# R131C.net
KiCad netlist of a schematic drawn in EAGLE
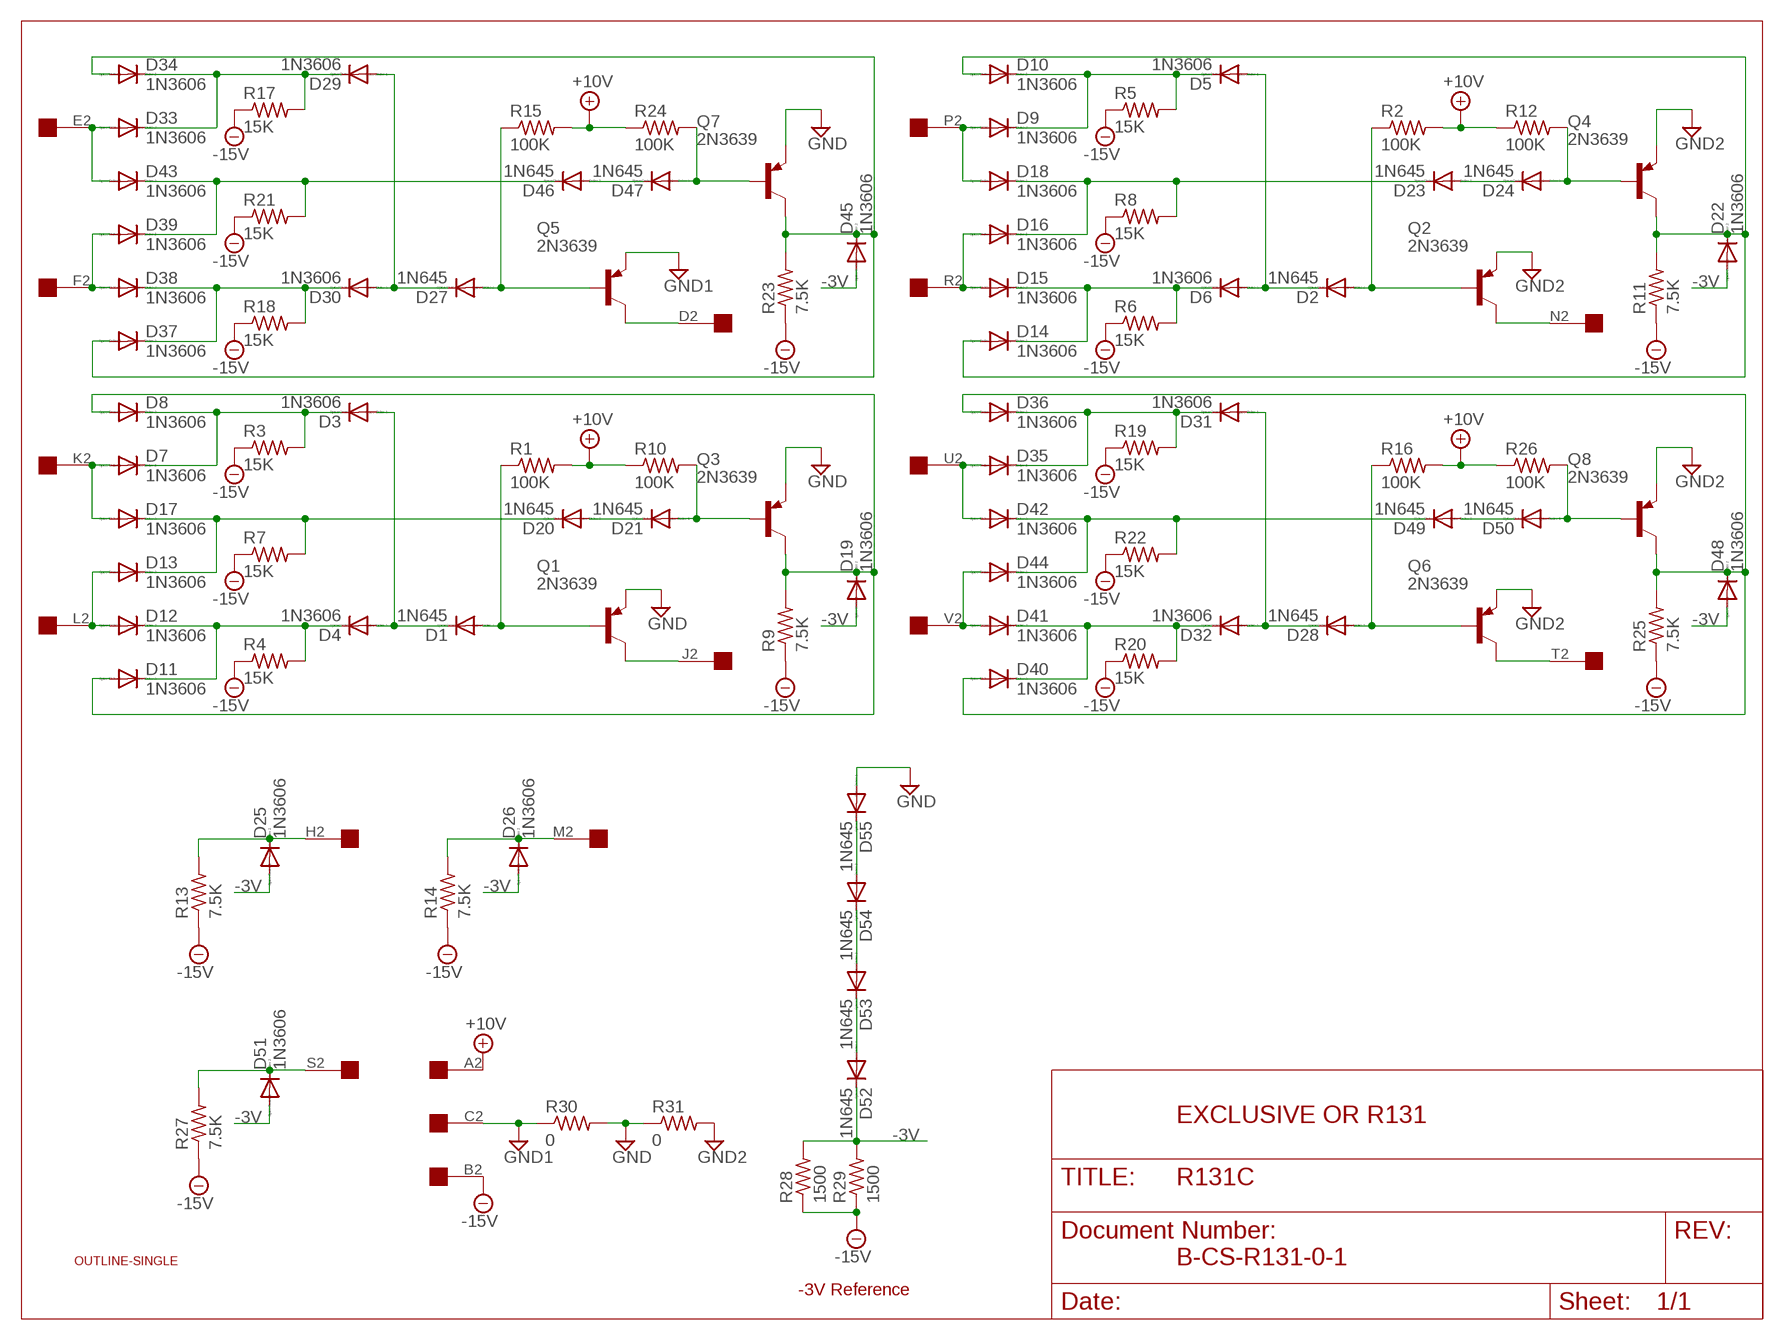
[diagram p0: schematic, sheet 1]

(export (version "E")
  (design (tool "Eeschema 10.0.6"))
  (components
    (comp (ref "D1")
      (value "1N645")
      (footprint "eagle-import:DO35-10")
      (libsource (lib "eagle-import") (part "1N4148DO35-10"))
    )
    (comp (ref "D2")
      (value "1N645")
      (footprint "eagle-import:DO35-10")
      (libsource (lib "eagle-import") (part "1N4148DO35-10"))
    )
    (comp (ref "D3")
      (value "1N3606")
      (footprint "eagle-import:DO35-10")
      (libsource (lib "eagle-import") (part "1N4148DO35-10"))
    )
    (comp (ref "D4")
      (value "1N3606")
      (footprint "eagle-import:DO35-10")
      (libsource (lib "eagle-import") (part "1N4148DO35-10"))
    )
    (comp (ref "D5")
      (value "1N3606")
      (footprint "eagle-import:DO35-10")
      (libsource (lib "eagle-import") (part "1N4148DO35-10"))
    )
    (comp (ref "D6")
      (value "1N3606")
      (footprint "eagle-import:DO35-10")
      (libsource (lib "eagle-import") (part "1N4148DO35-10"))
    )
    (comp (ref "D7")
      (value "1N3606")
      (footprint "eagle-import:DO35-10")
      (libsource (lib "eagle-import") (part "1N4148DO35-10"))
    )
    (comp (ref "D8")
      (value "1N3606")
      (footprint "eagle-import:DO35-10")
      (libsource (lib "eagle-import") (part "1N4148DO35-10"))
    )
    (comp (ref "D9")
      (value "1N3606")
      (footprint "eagle-import:DO35-10")
      (libsource (lib "eagle-import") (part "1N4148DO35-10"))
    )
    (comp (ref "D10")
      (value "1N3606")
      (footprint "eagle-import:DO35-10")
      (libsource (lib "eagle-import") (part "1N4148DO35-10"))
    )
    (comp (ref "D11")
      (value "1N3606")
      (footprint "eagle-import:DO35-10")
      (libsource (lib "eagle-import") (part "1N4148DO35-10"))
    )
    (comp (ref "D12")
      (value "1N3606")
      (footprint "eagle-import:DO35-10")
      (libsource (lib "eagle-import") (part "1N4148DO35-10"))
    )
    (comp (ref "D13")
      (value "1N3606")
      (footprint "eagle-import:DO35-10")
      (libsource (lib "eagle-import") (part "1N4148DO35-10"))
    )
    (comp (ref "D14")
      (value "1N3606")
      (footprint "eagle-import:DO35-10")
      (libsource (lib "eagle-import") (part "1N4148DO35-10"))
    )
    (comp (ref "D15")
      (value "1N3606")
      (footprint "eagle-import:DO35-10")
      (libsource (lib "eagle-import") (part "1N4148DO35-10"))
    )
    (comp (ref "D16")
      (value "1N3606")
      (footprint "eagle-import:DO35-10")
      (libsource (lib "eagle-import") (part "1N4148DO35-10"))
    )
    (comp (ref "D17")
      (value "1N3606")
      (footprint "eagle-import:DO35-10")
      (libsource (lib "eagle-import") (part "1N4148DO35-10"))
    )
    (comp (ref "D18")
      (value "1N3606")
      (footprint "eagle-import:DO35-10")
      (libsource (lib "eagle-import") (part "1N4148DO35-10"))
    )
    (comp (ref "D19")
      (value "1N3606")
      (footprint "eagle-import:DO35-10")
      (libsource (lib "eagle-import") (part "1N4148DO35-10"))
    )
    (comp (ref "D20")
      (value "1N645")
      (footprint "eagle-import:DO35-10")
      (libsource (lib "eagle-import") (part "1N4148DO35-10"))
    )
    (comp (ref "D21")
      (value "1N645")
      (footprint "eagle-import:DO35-10")
      (libsource (lib "eagle-import") (part "1N4148DO35-10"))
    )
    (comp (ref "D22")
      (value "1N3606")
      (footprint "eagle-import:DO35-10")
      (libsource (lib "eagle-import") (part "1N4148DO35-10"))
    )
    (comp (ref "D23")
      (value "1N645")
      (footprint "eagle-import:DO35-10")
      (libsource (lib "eagle-import") (part "1N4148DO35-10"))
    )
    (comp (ref "D24")
      (value "1N645")
      (footprint "eagle-import:DO35-10")
      (libsource (lib "eagle-import") (part "1N4148DO35-10"))
    )
    (comp (ref "D25")
      (value "1N3606")
      (footprint "eagle-import:DO35-10")
      (libsource (lib "eagle-import") (part "1N4148DO35-10"))
    )
    (comp (ref "D26")
      (value "1N3606")
      (footprint "eagle-import:DO35-10")
      (libsource (lib "eagle-import") (part "1N4148DO35-10"))
    )
    (comp (ref "D27")
      (value "1N645")
      (footprint "eagle-import:DO35-10")
      (libsource (lib "eagle-import") (part "1N4148DO35-10"))
    )
    (comp (ref "D28")
      (value "1N645")
      (footprint "eagle-import:DO35-10")
      (libsource (lib "eagle-import") (part "1N4148DO35-10"))
    )
    (comp (ref "D29")
      (value "1N3606")
      (footprint "eagle-import:DO35-10")
      (libsource (lib "eagle-import") (part "1N4148DO35-10"))
    )
    (comp (ref "D30")
      (value "1N3606")
      (footprint "eagle-import:DO35-10")
      (libsource (lib "eagle-import") (part "1N4148DO35-10"))
    )
    (comp (ref "D31")
      (value "1N3606")
      (footprint "eagle-import:DO35-10")
      (libsource (lib "eagle-import") (part "1N4148DO35-10"))
    )
    (comp (ref "D32")
      (value "1N3606")
      (footprint "eagle-import:DO35-10")
      (libsource (lib "eagle-import") (part "1N4148DO35-10"))
    )
    (comp (ref "D33")
      (value "1N3606")
      (footprint "eagle-import:DO35-10")
      (libsource (lib "eagle-import") (part "1N4148DO35-10"))
    )
    (comp (ref "D34")
      (value "1N3606")
      (footprint "eagle-import:DO35-10")
      (libsource (lib "eagle-import") (part "1N4148DO35-10"))
    )
    (comp (ref "D35")
      (value "1N3606")
      (footprint "eagle-import:DO35-10")
      (libsource (lib "eagle-import") (part "1N4148DO35-10"))
    )
    (comp (ref "D36")
      (value "1N3606")
      (footprint "eagle-import:DO35-10")
      (libsource (lib "eagle-import") (part "1N4148DO35-10"))
    )
    (comp (ref "D37")
      (value "1N3606")
      (footprint "eagle-import:DO35-10")
      (libsource (lib "eagle-import") (part "1N4148DO35-10"))
    )
    (comp (ref "D38")
      (value "1N3606")
      (footprint "eagle-import:DO35-10")
      (libsource (lib "eagle-import") (part "1N4148DO35-10"))
    )
    (comp (ref "D39")
      (value "1N3606")
      (footprint "eagle-import:DO35-10")
      (libsource (lib "eagle-import") (part "1N4148DO35-10"))
    )
    (comp (ref "D40")
      (value "1N3606")
      (footprint "eagle-import:DO35-10")
      (libsource (lib "eagle-import") (part "1N4148DO35-10"))
    )
    (comp (ref "D41")
      (value "1N3606")
      (footprint "eagle-import:DO35-10")
      (libsource (lib "eagle-import") (part "1N4148DO35-10"))
    )
    (comp (ref "D42")
      (value "1N3606")
      (footprint "eagle-import:DO35-10")
      (libsource (lib "eagle-import") (part "1N4148DO35-10"))
    )
    (comp (ref "D43")
      (value "1N3606")
      (footprint "eagle-import:DO35-10")
      (libsource (lib "eagle-import") (part "1N4148DO35-10"))
    )
    (comp (ref "D44")
      (value "1N3606")
      (footprint "eagle-import:DO35-10")
      (libsource (lib "eagle-import") (part "1N4148DO35-10"))
    )
    (comp (ref "D45")
      (value "1N3606")
      (footprint "eagle-import:DO35-10")
      (libsource (lib "eagle-import") (part "1N4148DO35-10"))
    )
    (comp (ref "D46")
      (value "1N645")
      (footprint "eagle-import:DO35-10")
      (libsource (lib "eagle-import") (part "1N4148DO35-10"))
    )
    (comp (ref "D47")
      (value "1N645")
      (footprint "eagle-import:DO35-10")
      (libsource (lib "eagle-import") (part "1N4148DO35-10"))
    )
    (comp (ref "D48")
      (value "1N3606")
      (footprint "eagle-import:DO35-10")
      (libsource (lib "eagle-import") (part "1N4148DO35-10"))
    )
    (comp (ref "D49")
      (value "1N645")
      (footprint "eagle-import:DO35-10")
      (libsource (lib "eagle-import") (part "1N4148DO35-10"))
    )
    (comp (ref "D50")
      (value "1N645")
      (footprint "eagle-import:DO35-10")
      (libsource (lib "eagle-import") (part "1N4148DO35-10"))
    )
    (comp (ref "D51")
      (value "1N3606")
      (footprint "eagle-import:DO35-10")
      (libsource (lib "eagle-import") (part "1N4148DO35-10"))
    )
    (comp (ref "D52")
      (value "1N645")
      (footprint "eagle-import:DO35-10")
      (libsource (lib "eagle-import") (part "1N4148DO35-10"))
    )
    (comp (ref "D53")
      (value "1N645")
      (footprint "eagle-import:DO35-10")
      (libsource (lib "eagle-import") (part "1N4148DO35-10"))
    )
    (comp (ref "D54")
      (value "1N645")
      (footprint "eagle-import:DO35-10")
      (libsource (lib "eagle-import") (part "1N4148DO35-10"))
    )
    (comp (ref "D55")
      (value "1N645")
      (footprint "eagle-import:DO35-10")
      (libsource (lib "eagle-import") (part "1N4148DO35-10"))
    )
    (comp (ref "Q1")
      (value "2N3639")
      (footprint "eagle-import:TO39")
      (libsource (lib "eagle-import") (part "2N3637"))
    )
    (comp (ref "Q2")
      (value "2N3639")
      (footprint "eagle-import:TO39")
      (libsource (lib "eagle-import") (part "2N3637"))
    )
    (comp (ref "Q3")
      (value "2N3639")
      (footprint "eagle-import:TO39")
      (libsource (lib "eagle-import") (part "2N3637"))
    )
    (comp (ref "Q4")
      (value "2N3639")
      (footprint "eagle-import:TO39")
      (libsource (lib "eagle-import") (part "2N3637"))
    )
    (comp (ref "Q5")
      (value "2N3639")
      (footprint "eagle-import:TO39")
      (libsource (lib "eagle-import") (part "2N3637"))
    )
    (comp (ref "Q6")
      (value "2N3639")
      (footprint "eagle-import:TO39")
      (libsource (lib "eagle-import") (part "2N3637"))
    )
    (comp (ref "Q7")
      (value "2N3639")
      (footprint "eagle-import:TO39")
      (libsource (lib "eagle-import") (part "2N3637"))
    )
    (comp (ref "Q8")
      (value "2N3639")
      (footprint "eagle-import:TO39")
      (libsource (lib "eagle-import") (part "2N3637"))
    )
    (comp (ref "R1")
      (value "100K")
      (footprint "eagle-import:0207_10")
      (libsource (lib "eagle-import") (part "R-US_0207/10"))
    )
    (comp (ref "R2")
      (value "100K")
      (footprint "eagle-import:0207_10")
      (libsource (lib "eagle-import") (part "R-US_0207/10"))
    )
    (comp (ref "R3")
      (value "15K")
      (footprint "eagle-import:0207_10")
      (libsource (lib "eagle-import") (part "R-US_0207/10"))
    )
    (comp (ref "R4")
      (value "15K")
      (footprint "eagle-import:0207_10")
      (libsource (lib "eagle-import") (part "R-US_0207/10"))
    )
    (comp (ref "R5")
      (value "15K")
      (footprint "eagle-import:0207_10")
      (libsource (lib "eagle-import") (part "R-US_0207/10"))
    )
    (comp (ref "R6")
      (value "15K")
      (footprint "eagle-import:0207_10")
      (libsource (lib "eagle-import") (part "R-US_0207/10"))
    )
    (comp (ref "R7")
      (value "15K")
      (footprint "eagle-import:0207_10")
      (libsource (lib "eagle-import") (part "R-US_0207/10"))
    )
    (comp (ref "R8")
      (value "15K")
      (footprint "eagle-import:0207_10")
      (libsource (lib "eagle-import") (part "R-US_0207/10"))
    )
    (comp (ref "R9")
      (value "7.5K")
      (footprint "eagle-import:0207_10")
      (libsource (lib "eagle-import") (part "R-US_0207/10"))
    )
    (comp (ref "R10")
      (value "100K")
      (footprint "eagle-import:0207_10")
      (libsource (lib "eagle-import") (part "R-US_0207/10"))
    )
    (comp (ref "R11")
      (value "7.5K")
      (footprint "eagle-import:0207_10")
      (libsource (lib "eagle-import") (part "R-US_0207/10"))
    )
    (comp (ref "R12")
      (value "100K")
      (footprint "eagle-import:0207_10")
      (libsource (lib "eagle-import") (part "R-US_0207/10"))
    )
    (comp (ref "R13")
      (value "7.5K")
      (footprint "eagle-import:0207_10")
      (libsource (lib "eagle-import") (part "R-US_0207/10"))
    )
    (comp (ref "R14")
      (value "7.5K")
      (footprint "eagle-import:0207_10")
      (libsource (lib "eagle-import") (part "R-US_0207/10"))
    )
    (comp (ref "R15")
      (value "100K")
      (footprint "eagle-import:0207_10")
      (libsource (lib "eagle-import") (part "R-US_0207/10"))
    )
    (comp (ref "R16")
      (value "100K")
      (footprint "eagle-import:0207_10")
      (libsource (lib "eagle-import") (part "R-US_0207/10"))
    )
    (comp (ref "R17")
      (value "15K")
      (footprint "eagle-import:0207_10")
      (libsource (lib "eagle-import") (part "R-US_0207/10"))
    )
    (comp (ref "R18")
      (value "15K")
      (footprint "eagle-import:0207_10")
      (libsource (lib "eagle-import") (part "R-US_0207/10"))
    )
    (comp (ref "R19")
      (value "15K")
      (footprint "eagle-import:0207_10")
      (libsource (lib "eagle-import") (part "R-US_0207/10"))
    )
    (comp (ref "R20")
      (value "15K")
      (footprint "eagle-import:0207_10")
      (libsource (lib "eagle-import") (part "R-US_0207/10"))
    )
    (comp (ref "R21")
      (value "15K")
      (footprint "eagle-import:0207_10")
      (libsource (lib "eagle-import") (part "R-US_0207/10"))
    )
    (comp (ref "R22")
      (value "15K")
      (footprint "eagle-import:0207_10")
      (libsource (lib "eagle-import") (part "R-US_0207/10"))
    )
    (comp (ref "R23")
      (value "7.5K")
      (footprint "eagle-import:0207_10")
      (libsource (lib "eagle-import") (part "R-US_0207/10"))
    )
    (comp (ref "R24")
      (value "100K")
      (footprint "eagle-import:0207_10")
      (libsource (lib "eagle-import") (part "R-US_0207/10"))
    )
    (comp (ref "R25")
      (value "7.5K")
      (footprint "eagle-import:0207_10")
      (libsource (lib "eagle-import") (part "R-US_0207/10"))
    )
    (comp (ref "R26")
      (value "100K")
      (footprint "eagle-import:0207_10")
      (libsource (lib "eagle-import") (part "R-US_0207/10"))
    )
    (comp (ref "R27")
      (value "7.5K")
      (footprint "eagle-import:0207_10")
      (libsource (lib "eagle-import") (part "R-US_0207/10"))
    )
    (comp (ref "R28")
      (value "1500")
      (footprint "eagle-import:0207_10")
      (libsource (lib "eagle-import") (part "R-US_0207/10"))
    )
    (comp (ref "R29")
      (value "1500")
      (footprint "eagle-import:0207_10")
      (libsource (lib "eagle-import") (part "R-US_0207/10"))
    )
    (comp (ref "R30")
      (value "0")
      (footprint "eagle-import:0207_10")
      (libsource (lib "eagle-import") (part "R-US_0207/10"))
    )
    (comp (ref "R31")
      (value "0")
      (footprint "eagle-import:0207_10")
      (libsource (lib "eagle-import") (part "R-US_0207/10"))
    )
    (comp (ref "U$1")
      (value "OUTLINE-SINGLE")
      (footprint "eagle-import:SINGLE")
      (libsource (lib "eagle-import") (part "OUTLINE-SINGLE"))
    )
    (comp (ref "U$2")
      (value "EDGE-1")
      (footprint "eagle-import:EDGE-CON1")
      (libsource (lib "eagle-import") (part "EDGE-1"))
    )
  )
  (nets
    (net (code "1") (name "+10V") (class "Default")
      (node (ref "R1") (pin "2") (pinfunction "2_2") (pintype "passive"))
      (node (ref "R10") (pin "1") (pinfunction "1_1") (pintype "passive"))
      (node (ref "R12") (pin "1") (pinfunction "1_1") (pintype "passive"))
      (node (ref "R15") (pin "2") (pinfunction "2_2") (pintype "passive"))
      (node (ref "R16") (pin "2") (pinfunction "2_2") (pintype "passive"))
      (node (ref "R2") (pin "2") (pinfunction "2_2") (pintype "passive"))
      (node (ref "R24") (pin "1") (pinfunction "1_1") (pintype "passive"))
      (node (ref "R26") (pin "1") (pinfunction "1_1") (pintype "passive"))
      (node (ref "U$2") (pin "A2") (pinfunction "1_A2") (pintype "bidirectional"))
    )
    (net (code "2") (name "-15V") (class "Default")
      (node (ref "R11") (pin "1") (pinfunction "1_1") (pintype "passive"))
      (node (ref "R13") (pin "1") (pinfunction "1_1") (pintype "passive"))
      (node (ref "R14") (pin "1") (pinfunction "1_1") (pintype "passive"))
      (node (ref "R17") (pin "1") (pinfunction "1_1") (pintype "passive"))
      (node (ref "R18") (pin "1") (pinfunction "1_1") (pintype "passive"))
      (node (ref "R19") (pin "1") (pinfunction "1_1") (pintype "passive"))
      (node (ref "R20") (pin "1") (pinfunction "1_1") (pintype "passive"))
      (node (ref "R21") (pin "1") (pinfunction "1_1") (pintype "passive"))
      (node (ref "R22") (pin "1") (pinfunction "1_1") (pintype "passive"))
      (node (ref "R23") (pin "1") (pinfunction "1_1") (pintype "passive"))
      (node (ref "R25") (pin "1") (pinfunction "1_1") (pintype "passive"))
      (node (ref "R27") (pin "1") (pinfunction "1_1") (pintype "passive"))
      (node (ref "R28") (pin "1") (pinfunction "1_1") (pintype "passive"))
      (node (ref "R29") (pin "1") (pinfunction "1_1") (pintype "passive"))
      (node (ref "R3") (pin "1") (pinfunction "1_1") (pintype "passive"))
      (node (ref "R4") (pin "1") (pinfunction "1_1") (pintype "passive"))
      (node (ref "R5") (pin "1") (pinfunction "1_1") (pintype "passive"))
      (node (ref "R6") (pin "1") (pinfunction "1_1") (pintype "passive"))
      (node (ref "R7") (pin "1") (pinfunction "1_1") (pintype "passive"))
      (node (ref "R8") (pin "1") (pinfunction "1_1") (pintype "passive"))
      (node (ref "R9") (pin "1") (pinfunction "1_1") (pintype "passive"))
      (node (ref "U$2") (pin "B2") (pinfunction "1_B2") (pintype "bidirectional"))
    )
    (net (code "3") (name "/-3V") (class "Default")
      (node (ref "D19") (pin "A") (pinfunction "A_A") (pintype "passive"))
      (node (ref "D22") (pin "A") (pinfunction "A_A") (pintype "passive"))
      (node (ref "D25") (pin "A") (pinfunction "A_A") (pintype "passive"))
      (node (ref "D26") (pin "A") (pinfunction "A_A") (pintype "passive"))
      (node (ref "D45") (pin "A") (pinfunction "A_A") (pintype "passive"))
      (node (ref "D48") (pin "A") (pinfunction "A_A") (pintype "passive"))
      (node (ref "D51") (pin "A") (pinfunction "A_A") (pintype "passive"))
      (node (ref "D52") (pin "C") (pinfunction "C_C") (pintype "passive"))
      (node (ref "R28") (pin "2") (pinfunction "2_2") (pintype "passive"))
      (node (ref "R29") (pin "2") (pinfunction "2_2") (pintype "passive"))
    )
    (net (code "4") (name "GND") (class "Default")
      (node (ref "D55") (pin "A") (pinfunction "A_A") (pintype "passive"))
      (node (ref "Q1") (pin "1") (pinfunction "E_1") (pintype "passive"))
      (node (ref "Q3") (pin "1") (pinfunction "E_1") (pintype "passive"))
      (node (ref "Q7") (pin "1") (pinfunction "E_1") (pintype "passive"))
      (node (ref "R30") (pin "2") (pinfunction "2_2") (pintype "passive"))
      (node (ref "R31") (pin "1") (pinfunction "1_1") (pintype "passive"))
    )
    (net (code "5") (name "GND1") (class "Default")
      (node (ref "Q5") (pin "1") (pinfunction "E_1") (pintype "passive"))
      (node (ref "R30") (pin "1") (pinfunction "1_1") (pintype "passive"))
      (node (ref "U$2") (pin "C2") (pinfunction "1_C2") (pintype "bidirectional"))
    )
    (net (code "6") (name "GND2") (class "Default")
      (node (ref "Q2") (pin "1") (pinfunction "E_1") (pintype "passive"))
      (node (ref "Q4") (pin "1") (pinfunction "E_1") (pintype "passive"))
      (node (ref "Q6") (pin "1") (pinfunction "E_1") (pintype "passive"))
      (node (ref "Q8") (pin "1") (pinfunction "E_1") (pintype "passive"))
      (node (ref "R31") (pin "2") (pinfunction "2_2") (pintype "passive"))
    )
    (net (code "7") (name "Net-(D1-PadC)") (class "Default")
      (node (ref "D1") (pin "C") (pinfunction "C_C") (pintype "passive"))
      (node (ref "D3") (pin "A") (pinfunction "A_A") (pintype "passive"))
      (node (ref "D4") (pin "A") (pinfunction "A_A") (pintype "passive"))
    )
    (net (code "8") (name "Net-(D2-PadC)") (class "Default")
      (node (ref "D2") (pin "C") (pinfunction "C_C") (pintype "passive"))
      (node (ref "D5") (pin "A") (pinfunction "A_A") (pintype "passive"))
      (node (ref "D6") (pin "A") (pinfunction "A_A") (pintype "passive"))
    )
    (net (code "9") (name "Net-(D3-PadC)") (class "Default")
      (node (ref "D3") (pin "C") (pinfunction "C_C") (pintype "passive"))
      (node (ref "D7") (pin "C") (pinfunction "C_C") (pintype "passive"))
      (node (ref "D8") (pin "C") (pinfunction "C_C") (pintype "passive"))
      (node (ref "R3") (pin "2") (pinfunction "2_2") (pintype "passive"))
    )
    (net (code "10") (name "Net-(D10-PadC)") (class "Default")
      (node (ref "D10") (pin "C") (pinfunction "C_C") (pintype "passive"))
      (node (ref "D5") (pin "C") (pinfunction "C_C") (pintype "passive"))
      (node (ref "D9") (pin "C") (pinfunction "C_C") (pintype "passive"))
      (node (ref "R5") (pin "2") (pinfunction "2_2") (pintype "passive"))
    )
    (net (code "11") (name "Net-(D11-PadC)") (class "Default")
      (node (ref "D11") (pin "C") (pinfunction "C_C") (pintype "passive"))
      (node (ref "D12") (pin "C") (pinfunction "C_C") (pintype "passive"))
      (node (ref "D4") (pin "C") (pinfunction "C_C") (pintype "passive"))
      (node (ref "R4") (pin "2") (pinfunction "2_2") (pintype "passive"))
    )
    (net (code "12") (name "Net-(D13-PadC)") (class "Default")
      (node (ref "D13") (pin "C") (pinfunction "C_C") (pintype "passive"))
      (node (ref "D17") (pin "C") (pinfunction "C_C") (pintype "passive"))
      (node (ref "D20") (pin "C") (pinfunction "C_C") (pintype "passive"))
      (node (ref "R7") (pin "2") (pinfunction "2_2") (pintype "passive"))
    )
    (net (code "13") (name "Net-(D14-PadC)") (class "Default")
      (node (ref "D14") (pin "C") (pinfunction "C_C") (pintype "passive"))
      (node (ref "D15") (pin "C") (pinfunction "C_C") (pintype "passive"))
      (node (ref "D6") (pin "C") (pinfunction "C_C") (pintype "passive"))
      (node (ref "R6") (pin "2") (pinfunction "2_2") (pintype "passive"))
    )
    (net (code "14") (name "Net-(D16-PadC)") (class "Default")
      (node (ref "D16") (pin "C") (pinfunction "C_C") (pintype "passive"))
      (node (ref "D18") (pin "C") (pinfunction "C_C") (pintype "passive"))
      (node (ref "D23") (pin "C") (pinfunction "C_C") (pintype "passive"))
      (node (ref "R8") (pin "2") (pinfunction "2_2") (pintype "passive"))
    )
    (net (code "15") (name "Net-(D20-PadA)") (class "Default")
      (node (ref "D20") (pin "A") (pinfunction "A_A") (pintype "passive"))
      (node (ref "D21") (pin "C") (pinfunction "C_C") (pintype "passive"))
    )
    (net (code "16") (name "Net-(D23-PadA)") (class "Default")
      (node (ref "D23") (pin "A") (pinfunction "A_A") (pintype "passive"))
      (node (ref "D24") (pin "C") (pinfunction "C_C") (pintype "passive"))
    )
    (net (code "17") (name "Net-(D27-PadC)") (class "Default")
      (node (ref "D27") (pin "C") (pinfunction "C_C") (pintype "passive"))
      (node (ref "D29") (pin "A") (pinfunction "A_A") (pintype "passive"))
      (node (ref "D30") (pin "A") (pinfunction "A_A") (pintype "passive"))
    )
    (net (code "18") (name "Net-(D28-PadC)") (class "Default")
      (node (ref "D28") (pin "C") (pinfunction "C_C") (pintype "passive"))
      (node (ref "D31") (pin "A") (pinfunction "A_A") (pintype "passive"))
      (node (ref "D32") (pin "A") (pinfunction "A_A") (pintype "passive"))
    )
    (net (code "19") (name "Net-(D29-PadC)") (class "Default")
      (node (ref "D29") (pin "C") (pinfunction "C_C") (pintype "passive"))
      (node (ref "D33") (pin "C") (pinfunction "C_C") (pintype "passive"))
      (node (ref "D34") (pin "C") (pinfunction "C_C") (pintype "passive"))
      (node (ref "R17") (pin "2") (pinfunction "2_2") (pintype "passive"))
    )
    (net (code "20") (name "Net-(D30-PadC)") (class "Default")
      (node (ref "D30") (pin "C") (pinfunction "C_C") (pintype "passive"))
      (node (ref "D37") (pin "C") (pinfunction "C_C") (pintype "passive"))
      (node (ref "D38") (pin "C") (pinfunction "C_C") (pintype "passive"))
      (node (ref "R18") (pin "2") (pinfunction "2_2") (pintype "passive"))
    )
    (net (code "21") (name "Net-(D31-PadC)") (class "Default")
      (node (ref "D31") (pin "C") (pinfunction "C_C") (pintype "passive"))
      (node (ref "D35") (pin "C") (pinfunction "C_C") (pintype "passive"))
      (node (ref "D36") (pin "C") (pinfunction "C_C") (pintype "passive"))
      (node (ref "R19") (pin "2") (pinfunction "2_2") (pintype "passive"))
    )
    (net (code "22") (name "Net-(D32-PadC)") (class "Default")
      (node (ref "D32") (pin "C") (pinfunction "C_C") (pintype "passive"))
      (node (ref "D40") (pin "C") (pinfunction "C_C") (pintype "passive"))
      (node (ref "D41") (pin "C") (pinfunction "C_C") (pintype "passive"))
      (node (ref "R20") (pin "2") (pinfunction "2_2") (pintype "passive"))
    )
    (net (code "23") (name "Net-(D39-PadC)") (class "Default")
      (node (ref "D39") (pin "C") (pinfunction "C_C") (pintype "passive"))
      (node (ref "D43") (pin "C") (pinfunction "C_C") (pintype "passive"))
      (node (ref "D46") (pin "C") (pinfunction "C_C") (pintype "passive"))
      (node (ref "R21") (pin "2") (pinfunction "2_2") (pintype "passive"))
    )
    (net (code "24") (name "Net-(D42-PadC)") (class "Default")
      (node (ref "D42") (pin "C") (pinfunction "C_C") (pintype "passive"))
      (node (ref "D44") (pin "C") (pinfunction "C_C") (pintype "passive"))
      (node (ref "D49") (pin "C") (pinfunction "C_C") (pintype "passive"))
      (node (ref "R22") (pin "2") (pinfunction "2_2") (pintype "passive"))
    )
    (net (code "25") (name "Net-(D46-PadA)") (class "Default")
      (node (ref "D46") (pin "A") (pinfunction "A_A") (pintype "passive"))
      (node (ref "D47") (pin "C") (pinfunction "C_C") (pintype "passive"))
    )
    (net (code "26") (name "Net-(D49-PadA)") (class "Default")
      (node (ref "D49") (pin "A") (pinfunction "A_A") (pintype "passive"))
      (node (ref "D50") (pin "C") (pinfunction "C_C") (pintype "passive"))
    )
    (net (code "27") (name "Net-(D52-PadA)") (class "Default")
      (node (ref "D52") (pin "A") (pinfunction "A_A") (pintype "passive"))
      (node (ref "D53") (pin "C") (pinfunction "C_C") (pintype "passive"))
    )
    (net (code "28") (name "Net-(D53-PadA)") (class "Default")
      (node (ref "D53") (pin "A") (pinfunction "A_A") (pintype "passive"))
      (node (ref "D54") (pin "C") (pinfunction "C_C") (pintype "passive"))
    )
    (net (code "29") (name "Net-(D54-PadA)") (class "Default")
      (node (ref "D54") (pin "A") (pinfunction "A_A") (pintype "passive"))
      (node (ref "D55") (pin "C") (pinfunction "C_C") (pintype "passive"))
    )
    (net (code "30") (name "Net-(Q1-B)") (class "Default")
      (node (ref "D1") (pin "A") (pinfunction "A_A") (pintype "passive"))
      (node (ref "Q1") (pin "2") (pinfunction "B_2") (pintype "passive"))
      (node (ref "R1") (pin "1") (pinfunction "1_1") (pintype "passive"))
    )
    (net (code "31") (name "Net-(Q1-C)") (class "Default")
      (node (ref "Q1") (pin "3") (pinfunction "C_3") (pintype "passive"))
      (node (ref "U$2") (pin "J2") (pinfunction "1_J2") (pintype "bidirectional"))
    )
    (net (code "32") (name "Net-(Q2-B)") (class "Default")
      (node (ref "D2") (pin "A") (pinfunction "A_A") (pintype "passive"))
      (node (ref "Q2") (pin "2") (pinfunction "B_2") (pintype "passive"))
      (node (ref "R2") (pin "1") (pinfunction "1_1") (pintype "passive"))
    )
    (net (code "33") (name "Net-(Q2-C)") (class "Default")
      (node (ref "Q2") (pin "3") (pinfunction "C_3") (pintype "passive"))
      (node (ref "U$2") (pin "N2") (pinfunction "1_N2") (pintype "bidirectional"))
    )
    (net (code "34") (name "Net-(Q3-B)") (class "Default")
      (node (ref "D21") (pin "A") (pinfunction "A_A") (pintype "passive"))
      (node (ref "Q3") (pin "2") (pinfunction "B_2") (pintype "passive"))
      (node (ref "R10") (pin "2") (pinfunction "2_2") (pintype "passive"))
    )
    (net (code "35") (name "Net-(Q3-C)") (class "Default")
      (node (ref "D11") (pin "A") (pinfunction "A_A") (pintype "passive"))
      (node (ref "D19") (pin "C") (pinfunction "C_C") (pintype "passive"))
      (node (ref "D8") (pin "A") (pinfunction "A_A") (pintype "passive"))
      (node (ref "Q3") (pin "3") (pinfunction "C_3") (pintype "passive"))
      (node (ref "R9") (pin "2") (pinfunction "2_2") (pintype "passive"))
    )
    (net (code "36") (name "Net-(Q4-B)") (class "Default")
      (node (ref "D24") (pin "A") (pinfunction "A_A") (pintype "passive"))
      (node (ref "Q4") (pin "2") (pinfunction "B_2") (pintype "passive"))
      (node (ref "R12") (pin "2") (pinfunction "2_2") (pintype "passive"))
    )
    (net (code "37") (name "Net-(Q4-C)") (class "Default")
      (node (ref "D10") (pin "A") (pinfunction "A_A") (pintype "passive"))
      (node (ref "D14") (pin "A") (pinfunction "A_A") (pintype "passive"))
      (node (ref "D22") (pin "C") (pinfunction "C_C") (pintype "passive"))
      (node (ref "Q4") (pin "3") (pinfunction "C_3") (pintype "passive"))
      (node (ref "R11") (pin "2") (pinfunction "2_2") (pintype "passive"))
    )
    (net (code "38") (name "Net-(Q5-B)") (class "Default")
      (node (ref "D27") (pin "A") (pinfunction "A_A") (pintype "passive"))
      (node (ref "Q5") (pin "2") (pinfunction "B_2") (pintype "passive"))
      (node (ref "R15") (pin "1") (pinfunction "1_1") (pintype "passive"))
    )
    (net (code "39") (name "Net-(Q5-C)") (class "Default")
      (node (ref "Q5") (pin "3") (pinfunction "C_3") (pintype "passive"))
      (node (ref "U$2") (pin "D2") (pinfunction "1_D2") (pintype "bidirectional"))
    )
    (net (code "40") (name "Net-(Q6-B)") (class "Default")
      (node (ref "D28") (pin "A") (pinfunction "A_A") (pintype "passive"))
      (node (ref "Q6") (pin "2") (pinfunction "B_2") (pintype "passive"))
      (node (ref "R16") (pin "1") (pinfunction "1_1") (pintype "passive"))
    )
    (net (code "41") (name "Net-(Q6-C)") (class "Default")
      (node (ref "Q6") (pin "3") (pinfunction "C_3") (pintype "passive"))
      (node (ref "U$2") (pin "T2") (pinfunction "1_T2") (pintype "bidirectional"))
    )
    (net (code "42") (name "Net-(Q7-B)") (class "Default")
      (node (ref "D47") (pin "A") (pinfunction "A_A") (pintype "passive"))
      (node (ref "Q7") (pin "2") (pinfunction "B_2") (pintype "passive"))
      (node (ref "R24") (pin "2") (pinfunction "2_2") (pintype "passive"))
    )
    (net (code "43") (name "Net-(Q7-C)") (class "Default")
      (node (ref "D34") (pin "A") (pinfunction "A_A") (pintype "passive"))
      (node (ref "D37") (pin "A") (pinfunction "A_A") (pintype "passive"))
      (node (ref "D45") (pin "C") (pinfunction "C_C") (pintype "passive"))
      (node (ref "Q7") (pin "3") (pinfunction "C_3") (pintype "passive"))
      (node (ref "R23") (pin "2") (pinfunction "2_2") (pintype "passive"))
    )
    (net (code "44") (name "Net-(Q8-B)") (class "Default")
      (node (ref "D50") (pin "A") (pinfunction "A_A") (pintype "passive"))
      (node (ref "Q8") (pin "2") (pinfunction "B_2") (pintype "passive"))
      (node (ref "R26") (pin "2") (pinfunction "2_2") (pintype "passive"))
    )
    (net (code "45") (name "Net-(Q8-C)") (class "Default")
      (node (ref "D36") (pin "A") (pinfunction "A_A") (pintype "passive"))
      (node (ref "D40") (pin "A") (pinfunction "A_A") (pintype "passive"))
      (node (ref "D48") (pin "C") (pinfunction "C_C") (pintype "passive"))
      (node (ref "Q8") (pin "3") (pinfunction "C_3") (pintype "passive"))
      (node (ref "R25") (pin "2") (pinfunction "2_2") (pintype "passive"))
    )
    (net (code "46") (name "Net-(U$2E-1)") (class "Default")
      (node (ref "D33") (pin "A") (pinfunction "A_A") (pintype "passive"))
      (node (ref "D43") (pin "A") (pinfunction "A_A") (pintype "passive"))
      (node (ref "U$2") (pin "E2") (pinfunction "1_E2") (pintype "bidirectional"))
    )
    (net (code "47") (name "Net-(U$2F-1)") (class "Default")
      (node (ref "D38") (pin "A") (pinfunction "A_A") (pintype "passive"))
      (node (ref "D39") (pin "A") (pinfunction "A_A") (pintype "passive"))
      (node (ref "U$2") (pin "F2") (pinfunction "1_F2") (pintype "bidirectional"))
    )
    (net (code "48") (name "Net-(U$2G-1)") (class "Default")
      (node (ref "D25") (pin "C") (pinfunction "C_C") (pintype "passive"))
      (node (ref "R13") (pin "2") (pinfunction "2_2") (pintype "passive"))
      (node (ref "U$2") (pin "H2") (pinfunction "1_H2") (pintype "bidirectional"))
    )
    (net (code "49") (name "Net-(U$2I-1)") (class "Default")
      (node (ref "D17") (pin "A") (pinfunction "A_A") (pintype "passive"))
      (node (ref "D7") (pin "A") (pinfunction "A_A") (pintype "passive"))
      (node (ref "U$2") (pin "K2") (pinfunction "1_K2") (pintype "bidirectional"))
    )
    (net (code "50") (name "Net-(U$2J-1)") (class "Default")
      (node (ref "D12") (pin "A") (pinfunction "A_A") (pintype "passive"))
      (node (ref "D13") (pin "A") (pinfunction "A_A") (pintype "passive"))
      (node (ref "U$2") (pin "L2") (pinfunction "1_L2") (pintype "bidirectional"))
    )
    (net (code "51") (name "Net-(U$2K-1)") (class "Default")
      (node (ref "D26") (pin "C") (pinfunction "C_C") (pintype "passive"))
      (node (ref "R14") (pin "2") (pinfunction "2_2") (pintype "passive"))
      (node (ref "U$2") (pin "M2") (pinfunction "1_M2") (pintype "bidirectional"))
    )
    (net (code "52") (name "Net-(U$2M-1)") (class "Default")
      (node (ref "D18") (pin "A") (pinfunction "A_A") (pintype "passive"))
      (node (ref "D9") (pin "A") (pinfunction "A_A") (pintype "passive"))
      (node (ref "U$2") (pin "P2") (pinfunction "1_P2") (pintype "bidirectional"))
    )
    (net (code "53") (name "Net-(U$2N-1)") (class "Default")
      (node (ref "D15") (pin "A") (pinfunction "A_A") (pintype "passive"))
      (node (ref "D16") (pin "A") (pinfunction "A_A") (pintype "passive"))
      (node (ref "U$2") (pin "R2") (pinfunction "1_R2") (pintype "bidirectional"))
    )
    (net (code "54") (name "Net-(U$2O-1)") (class "Default")
      (node (ref "D51") (pin "C") (pinfunction "C_C") (pintype "passive"))
      (node (ref "R27") (pin "2") (pinfunction "2_2") (pintype "passive"))
      (node (ref "U$2") (pin "S2") (pinfunction "1_S2") (pintype "bidirectional"))
    )
    (net (code "55") (name "Net-(U$2Q-1)") (class "Default")
      (node (ref "D35") (pin "A") (pinfunction "A_A") (pintype "passive"))
      (node (ref "D42") (pin "A") (pinfunction "A_A") (pintype "passive"))
      (node (ref "U$2") (pin "U2") (pinfunction "1_U2") (pintype "bidirectional"))
    )
    (net (code "56") (name "Net-(U$2R-1)") (class "Default")
      (node (ref "D41") (pin "A") (pinfunction "A_A") (pintype "passive"))
      (node (ref "D44") (pin "A") (pinfunction "A_A") (pintype "passive"))
      (node (ref "U$2") (pin "V2") (pinfunction "1_V2") (pintype "bidirectional"))
    )
  )
)
